# fdcanusb.net
KiCad netlist of a schematic drawn in EAGLE
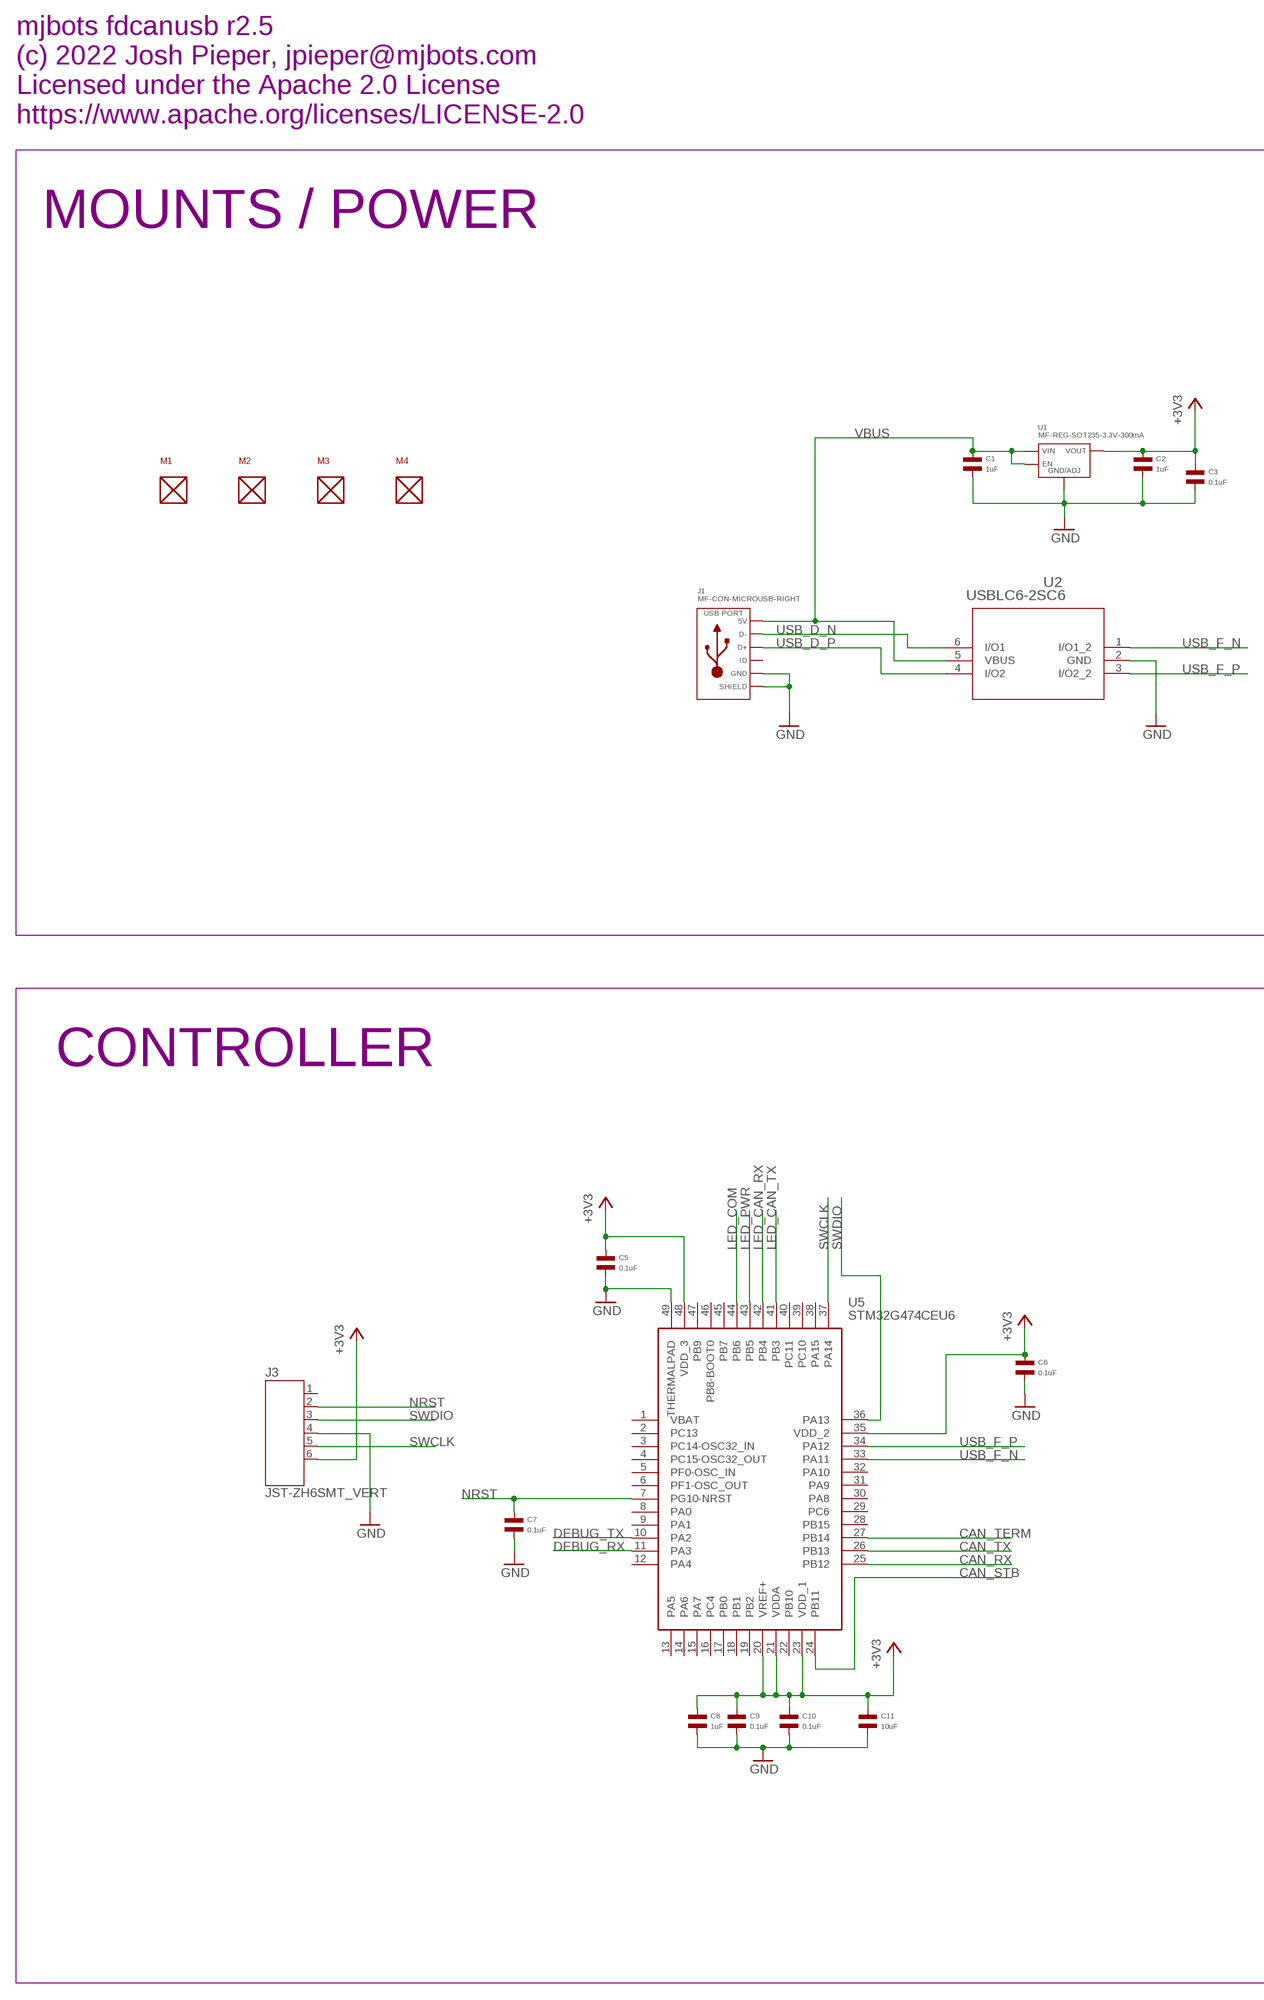
[diagram p0: schematic, sheet 1, part 1 of 2]
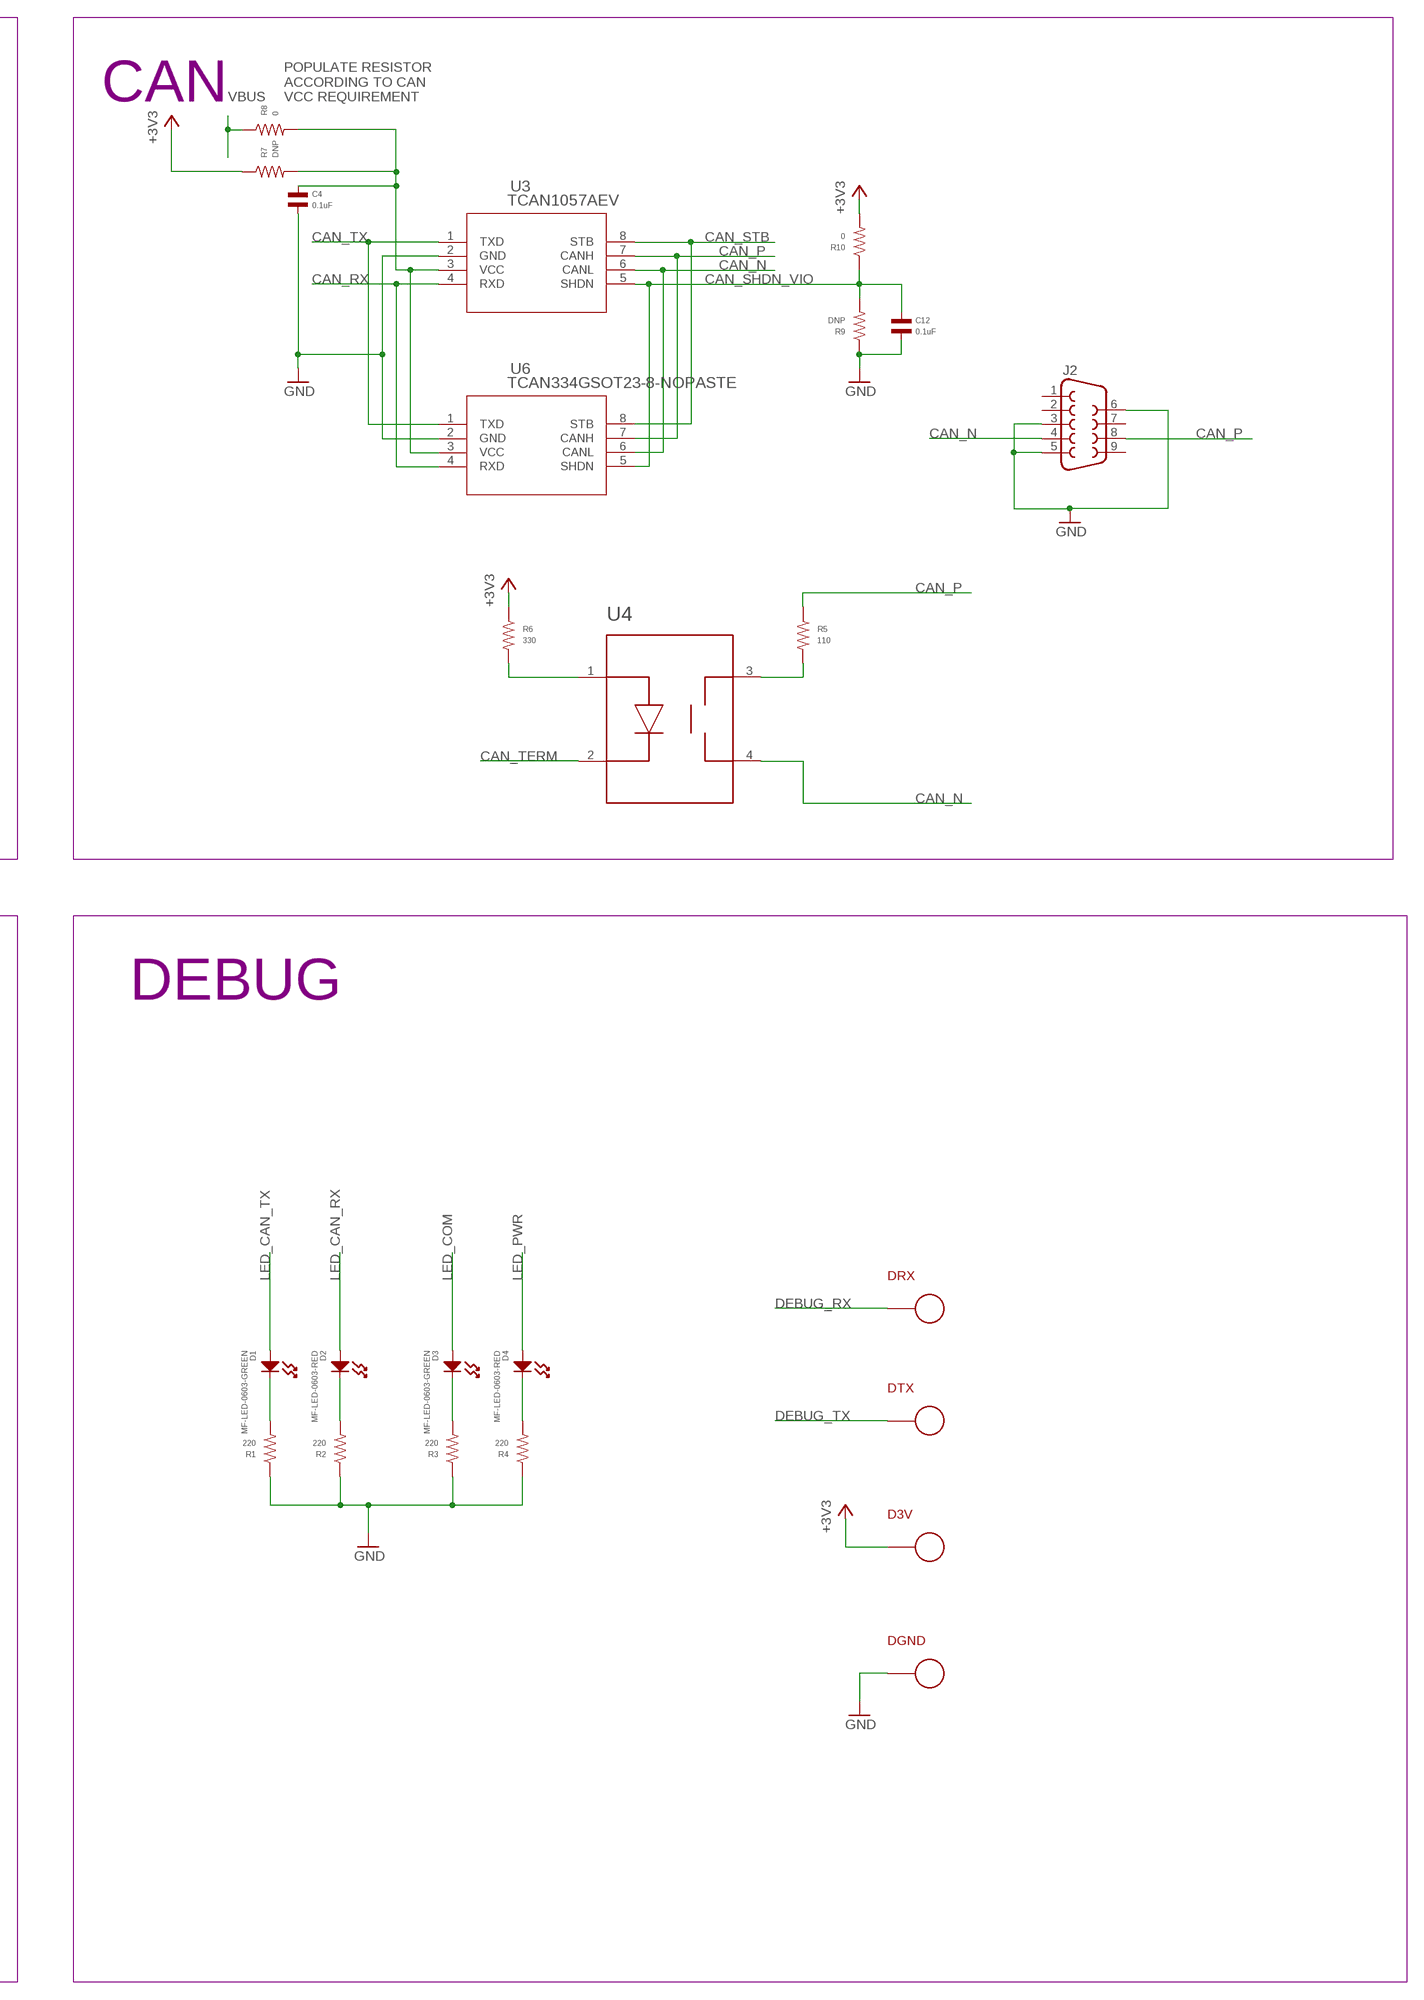
[diagram p1: schematic, sheet 1, part 2 of 2]

(export (version "E")
  (design (tool "Eeschema 10.0.6"))
  (components
    (comp (ref "C1")
      (value "1uF")
      (footprint "eagle-import:C0603")
      (fields (field (name "HOUSEPART") "YES") (field (name "MPN") "MF-CAP-0603-1uF"))
      (libsource (lib "eagle-import") (part "CAPACITOR_NP_0603"))
    )
    (comp (ref "C2")
      (value "1uF")
      (footprint "eagle-import:C0603")
      (fields (field (name "HOUSEPART") "YES") (field (name "MPN") "MF-CAP-0603-1uF"))
      (libsource (lib "eagle-import") (part "CAPACITOR_NP_0603"))
    )
    (comp (ref "C3")
      (value "0.1uF")
      (footprint "eagle-import:C0603")
      (fields (field (name "HOUSEPART") "YES") (field (name "MPN") "MF-CAP-0603-0.1uF"))
      (libsource (lib "eagle-import") (part "CAPACITOR_NP_0603"))
    )
    (comp (ref "C4")
      (value "0.1uF")
      (footprint "eagle-import:C0603")
      (fields (field (name "HOUSEPART") "YES") (field (name "MPN") "MF-CAP-0603-0.1uF"))
      (libsource (lib "eagle-import") (part "CAPACITOR_NP_0603"))
    )
    (comp (ref "C5")
      (value "0.1uF")
      (footprint "eagle-import:C0603")
      (fields (field (name "HOUSEPART") "YES") (field (name "MPN") "MF-CAP-0603-0.1uF"))
      (libsource (lib "eagle-import") (part "CAPACITOR_NP_0603"))
    )
    (comp (ref "C6")
      (value "0.1uF")
      (footprint "eagle-import:C0603")
      (fields (field (name "HOUSEPART") "YES") (field (name "MPN") "MF-CAP-0603-0.1uF"))
      (libsource (lib "eagle-import") (part "CAPACITOR_NP_0603"))
    )
    (comp (ref "C7")
      (value "0.1uF")
      (footprint "eagle-import:C0603")
      (fields (field (name "HOUSEPART") "YES") (field (name "MPN") "MF-CAP-0603-0.1uF"))
      (libsource (lib "eagle-import") (part "CAPACITOR_NP_0603"))
    )
    (comp (ref "C8")
      (value "1uF")
      (footprint "eagle-import:C0603")
      (fields (field (name "HOUSEPART") "YES") (field (name "MPN") "MF-CAP-0603-1uF"))
      (libsource (lib "eagle-import") (part "CAPACITOR_NP_0603"))
    )
    (comp (ref "C9")
      (value "0.1uF")
      (footprint "eagle-import:C0603")
      (fields (field (name "HOUSEPART") "YES") (field (name "MPN") "MF-CAP-0603-0.1uF"))
      (libsource (lib "eagle-import") (part "CAPACITOR_NP_0603"))
    )
    (comp (ref "C10")
      (value "0.1uF")
      (footprint "eagle-import:C0603")
      (fields (field (name "HOUSEPART") "YES") (field (name "MPN") "MF-CAP-0603-0.1uF"))
      (libsource (lib "eagle-import") (part "CAPACITOR_NP_0603"))
    )
    (comp (ref "C11")
      (value "10uF")
      (footprint "eagle-import:C1206")
      (fields (field (name "HOUSEPART") "YES") (field (name "MPN") "MF-CAP-1206-10uF"))
      (libsource (lib "eagle-import") (part "CAPACITOR_NP_1206"))
    )
    (comp (ref "C12")
      (value "0.1uF")
      (footprint "eagle-import:C0603")
      (fields (field (name "HOUSEPART") "YES") (field (name "MPN") "MF-CAP-0603-0.1uF"))
      (libsource (lib "eagle-import") (part "CAPACITOR_NP_0603"))
    )
    (comp (ref "D1")
      (value "MF-LED-0603-GREEN")
      (footprint "eagle-import:LED0603")
      (fields (field (name "HOUSEPART") "YES"))
      (libsource (lib "eagle-import") (part "LED_SINGLE-0603-GREEN"))
    )
    (comp (ref "D2")
      (value "MF-LED-0603-RED")
      (footprint "eagle-import:LED0603")
      (fields (field (name "HOUSEPART") "YES"))
      (libsource (lib "eagle-import") (part "LED_SINGLE-0603-RED"))
    )
    (comp (ref "D3")
      (value "MF-LED-0603-GREEN")
      (footprint "eagle-import:LED0603")
      (fields (field (name "HOUSEPART") "YES"))
      (libsource (lib "eagle-import") (part "LED_SINGLE-0603-GREEN"))
    )
    (comp (ref "D3V")
      (value "PAD24AWG_PAD")
      (footprint "eagle-import:24AWG_PAD")
      (libsource (lib "eagle-import") (part "PAD24AWG_PAD"))
    )
    (comp (ref "D4")
      (value "MF-LED-0603-RED")
      (footprint "eagle-import:LED0603")
      (fields (field (name "HOUSEPART") "YES"))
      (libsource (lib "eagle-import") (part "LED_SINGLE-0603-RED"))
    )
    (comp (ref "DGND")
      (value "PAD24AWG_PAD")
      (footprint "eagle-import:24AWG_PAD")
      (libsource (lib "eagle-import") (part "PAD24AWG_PAD"))
    )
    (comp (ref "DRX")
      (value "PAD24AWG_PAD")
      (footprint "eagle-import:24AWG_PAD")
      (libsource (lib "eagle-import") (part "PAD24AWG_PAD"))
    )
    (comp (ref "DTX")
      (value "PAD24AWG_PAD")
      (footprint "eagle-import:24AWG_PAD")
      (libsource (lib "eagle-import") (part "PAD24AWG_PAD"))
    )
    (comp (ref "J1")
      (value "MF-CON-MICROUSB-RIGHT")
      (footprint "eagle-import:MICROUSB-RIGHT")
      (fields (field (name "HOUSEPART") "YES"))
      (libsource (lib "eagle-import") (part "USB_MICRO_RIGHT"))
    )
    (comp (ref "J2")
      (value "F09")
      (footprint "eagle-import:DB09_PLATED")
      (libsource (lib "eagle-import") (part "F09"))
    )
    (comp (ref "J3")
      (value "JST-ZH6SMT_VERT")
      (footprint "eagle-import:JST_B6B-ZR-SM4-TF(LF)(SN)")
      (fields (field (name "MF") "JST") (field (name "MPN") "B6B-ZR-SM4-TF(LF)(SN)"))
      (libsource (lib "eagle-import") (part "JST-ZH6SMT_VERT"))
    )
    (comp (ref "M1")
      (value "MOUNT")
      (footprint "eagle-import:M2.5MOUNT")
      (libsource (lib "eagle-import") (part "MOUNT"))
    )
    (comp (ref "M2")
      (value "MOUNT")
      (footprint "eagle-import:M2.5MOUNT")
      (libsource (lib "eagle-import") (part "MOUNT"))
    )
    (comp (ref "M3")
      (value "MOUNT")
      (footprint "eagle-import:M2.5MOUNT")
      (libsource (lib "eagle-import") (part "MOUNT"))
    )
    (comp (ref "M4")
      (value "MOUNT")
      (footprint "eagle-import:M2.5MOUNT")
      (libsource (lib "eagle-import") (part "MOUNT"))
    )
    (comp (ref "R1")
      (value "220")
      (footprint "eagle-import:R0603")
      (fields (field (name "HOUSEPART") "YES") (field (name "MPN") "MF-RES-0603-220"))
      (libsource (lib "eagle-import") (part "RESISTOR_0603"))
    )
    (comp (ref "R2")
      (value "220")
      (footprint "eagle-import:R0603")
      (fields (field (name "HOUSEPART") "YES") (field (name "MPN") "MF-RES-0603-220"))
      (libsource (lib "eagle-import") (part "RESISTOR_0603"))
    )
    (comp (ref "R3")
      (value "220")
      (footprint "eagle-import:R0603")
      (fields (field (name "HOUSEPART") "YES") (field (name "MPN") "MF-RES-0603-220"))
      (libsource (lib "eagle-import") (part "RESISTOR_0603"))
    )
    (comp (ref "R4")
      (value "220")
      (footprint "eagle-import:R0603")
      (fields (field (name "HOUSEPART") "YES") (field (name "MPN") "MF-RES-0603-220"))
      (libsource (lib "eagle-import") (part "RESISTOR_0603"))
    )
    (comp (ref "R5")
      (value "110")
      (footprint "eagle-import:R0603")
      (fields (field (name "MF") "YAGEO") (field (name "MPN") "RC0603FR-07110RL"))
      (libsource (lib "eagle-import") (part "RESISTOR_0603"))
    )
    (comp (ref "R6")
      (value "330")
      (footprint "eagle-import:R0603")
      (fields (field (name "HOUSEPART") "YES") (field (name "MPN") "MF-RES-0603-330"))
      (libsource (lib "eagle-import") (part "RESISTOR_0603"))
    )
    (comp (ref "R7")
      (value "DNP")
      (footprint "eagle-import:R0603")
      (fields (field (name "HOUSEPART") "YES") (field (name "POPULATE") "0"))
      (libsource (lib "eagle-import") (part "RESISTOR_0603"))
    )
    (comp (ref "R8")
      (value "0")
      (footprint "eagle-import:R0603")
      (fields (field (name "HOUSEPART") "YES") (field (name "MPN") "MF-RES-0603-0"))
      (libsource (lib "eagle-import") (part "RESISTOR_0603"))
    )
    (comp (ref "R9")
      (value "DNP")
      (footprint "eagle-import:R0603")
      (fields (field (name "HOUSEPART") "YES") (field (name "POPULATE") "0"))
      (libsource (lib "eagle-import") (part "RESISTOR_0603"))
    )
    (comp (ref "R10")
      (value "0")
      (footprint "eagle-import:R0603")
      (fields (field (name "HOUSEPART") "YES") (field (name "MPN") "MF-RES-0603-0"))
      (libsource (lib "eagle-import") (part "RESISTOR_0603"))
    )
    (comp (ref "U1")
      (value "MF-REG-SOT235-3.3V-300mA")
      (footprint "eagle-import:SOT-23-5")
      (fields (field (name "HOUSEPART") "YES"))
      (libsource (lib "eagle-import") (part "TLV70233PDBVR"))
    )
    (comp (ref "U2")
      (value "USBLC6-2SC6")
      (footprint "eagle-import:SOT23-6L")
      (fields (field (name "MANUFACTURER_PART_NUMBER") "USBLC62SC6") (field (name "MF") "ST"))
      (libsource (lib "eagle-import") (part "USBLC6-2SC6"))
    )
    (comp (ref "U3")
      (value "TCAN1057AEV")
      (footprint "eagle-import:SOIC8")
      (fields (field (name "MF") "TI") (field (name "MPN") "TCAN1057AEVDRQ1"))
      (libsource (lib "eagle-import") (part "fdcanusb_TCAN334G"))
    )
    (comp (ref "U4")
      (value "TLP3317")
      (footprint "eagle-import:TLP3317")
      (fields
        (field (name "MF") "TOSHIBA")
        (field (name "MPN") "TLP3317(TP15,F")
        (field (name "MPN_1") "TLP3317")
      )
      (libsource (lib "eagle-import") (part "TLP3317"))
    )
    (comp (ref "U5")
      (value "STM32G474CEU6")
      (footprint "eagle-import:QFN50P700X700X60-49N")
      (fields (field (name "MOUSER_PART_NUMBER") "511-STM32G474CEU6") (field (name "MF") "ST"))
      (libsource (lib "eagle-import") (part "STM32G474CEU6"))
    )
    (comp (ref "U6")
      (value "TCAN334GSOT23-8-NOPASTE")
      (footprint "eagle-import:SOT23-8-NOPASTE")
      (fields (field (name "MF") "TI") (field (name "MPN") "TCAN334GDCNT"))
      (libsource (lib "eagle-import") (part "TCAN334GSOT23-8-NOPASTE"))
    )
  )
  (nets
    (net (code "1") (name "+3V3") (class "Default")
      (node (ref "C10") (pin "P$1") (pinfunction "P$1_P$1") (pintype "passive"))
      (node (ref "C11") (pin "P$1") (pinfunction "P$1_P$1") (pintype "passive"))
      (node (ref "C2") (pin "P$1") (pinfunction "P$1_P$1") (pintype "passive"))
      (node (ref "C3") (pin "P$1") (pinfunction "P$1_P$1") (pintype "passive"))
      (node (ref "C5") (pin "P$1") (pinfunction "P$1_P$1") (pintype "passive"))
      (node (ref "C6") (pin "P$1") (pinfunction "P$1_P$1") (pintype "passive"))
      (node (ref "C8") (pin "P$1") (pinfunction "P$1_P$1") (pintype "passive"))
      (node (ref "C9") (pin "P$1") (pinfunction "P$1_P$1") (pintype "passive"))
      (node (ref "D3V") (pin "P$1") (pinfunction "P$1_P$1") (pintype "bidirectional"))
      (node (ref "J3") (pin "6") (pinfunction "6_6") (pintype "passive"))
      (node (ref "R10") (pin "P$2") (pinfunction "P$2_P$2") (pintype "passive"))
      (node (ref "R6") (pin "P$1") (pinfunction "P$1_P$1") (pintype "passive"))
      (node (ref "R7") (pin "P$1") (pinfunction "P$1_P$1") (pintype "passive"))
      (node (ref "U1") (pin "P$5") (pinfunction "VOUT_P$5") (pintype "bidirectional"))
      (node (ref "U5") (pin "20") (pinfunction "VREF+_20") (pintype "bidirectional"))
      (node (ref "U5") (pin "21") (pinfunction "VDDA_21") (pintype "bidirectional"))
      (node (ref "U5") (pin "23") (pinfunction "VDD_1_23") (pintype "bidirectional"))
      (node (ref "U5") (pin "35") (pinfunction "VDD_2_35") (pintype "bidirectional"))
      (node (ref "U5") (pin "48") (pinfunction "VDD_3_48") (pintype "bidirectional"))
    )
    (net (code "2") (name "/CAN_N") (class "Default")
      (node (ref "J2") (pin "4") (pinfunction "4_4") (pintype "passive"))
      (node (ref "U3") (pin "6") (pinfunction "CANL_6") (pintype "bidirectional"))
      (node (ref "U4") (pin "4") (pinfunction "SW2_4") (pintype "bidirectional"))
      (node (ref "U6") (pin "6") (pinfunction "CANL_6") (pintype "bidirectional"))
    )
    (net (code "3") (name "/CAN_P") (class "Default")
      (node (ref "J2") (pin "8") (pinfunction "8_8") (pintype "passive"))
      (node (ref "R5") (pin "P$1") (pinfunction "P$1_P$1") (pintype "passive"))
      (node (ref "U3") (pin "7") (pinfunction "CANH_7") (pintype "bidirectional"))
      (node (ref "U6") (pin "7") (pinfunction "CANH_7") (pintype "bidirectional"))
    )
    (net (code "4") (name "/CAN_RX") (class "Default")
      (node (ref "U3") (pin "4") (pinfunction "RXD_4") (pintype "output"))
      (node (ref "U5") (pin "25") (pinfunction "PB12_25") (pintype "bidirectional"))
      (node (ref "U6") (pin "4") (pinfunction "RXD_4") (pintype "output"))
    )
    (net (code "5") (name "/CAN_SHDN_VIO") (class "Default")
      (node (ref "C12") (pin "P$1") (pinfunction "P$1_P$1") (pintype "passive"))
      (node (ref "R10") (pin "P$1") (pinfunction "P$1_P$1") (pintype "passive"))
      (node (ref "R9") (pin "P$2") (pinfunction "P$2_P$2") (pintype "passive"))
      (node (ref "U3") (pin "5") (pinfunction "SHDN_5") (pintype "input"))
      (node (ref "U6") (pin "5") (pinfunction "SHDN_5") (pintype "input"))
    )
    (net (code "6") (name "/CAN_STB") (class "Default")
      (node (ref "U3") (pin "8") (pinfunction "STB_8") (pintype "input"))
      (node (ref "U5") (pin "24") (pinfunction "PB11_24") (pintype "bidirectional"))
      (node (ref "U6") (pin "8") (pinfunction "STB_8") (pintype "input"))
    )
    (net (code "7") (name "/CAN_TERM") (class "Default")
      (node (ref "U4") (pin "2") (pinfunction "CATHODE_2") (pintype "bidirectional"))
      (node (ref "U5") (pin "27") (pinfunction "PB14_27") (pintype "bidirectional"))
    )
    (net (code "8") (name "/CAN_TX") (class "Default")
      (node (ref "U3") (pin "1") (pinfunction "TXD_1") (pintype "input"))
      (node (ref "U5") (pin "26") (pinfunction "PB13_26") (pintype "bidirectional"))
      (node (ref "U6") (pin "1") (pinfunction "TXD_1") (pintype "input"))
    )
    (net (code "9") (name "/DEBUG_RX") (class "Default")
      (node (ref "DRX") (pin "P$1") (pinfunction "P$1_P$1") (pintype "bidirectional"))
      (node (ref "U5") (pin "11") (pinfunction "PA3_11") (pintype "bidirectional"))
    )
    (net (code "10") (name "/DEBUG_TX") (class "Default")
      (node (ref "DTX") (pin "P$1") (pinfunction "P$1_P$1") (pintype "bidirectional"))
      (node (ref "U5") (pin "10") (pinfunction "PA2_10") (pintype "bidirectional"))
    )
    (net (code "11") (name "/LED_CAN_RX") (class "Default")
      (node (ref "D2") (pin "ANODE") (pinfunction "ANODE_ANODE") (pintype "power_in"))
      (node (ref "U5") (pin "42") (pinfunction "PB4_42") (pintype "bidirectional"))
    )
    (net (code "12") (name "/LED_CAN_TX") (class "Default")
      (node (ref "D1") (pin "ANODE") (pinfunction "ANODE_ANODE") (pintype "power_in"))
      (node (ref "U5") (pin "41") (pinfunction "PB3_41") (pintype "bidirectional"))
    )
    (net (code "13") (name "/LED_COM") (class "Default")
      (node (ref "D3") (pin "ANODE") (pinfunction "ANODE_ANODE") (pintype "power_in"))
      (node (ref "U5") (pin "44") (pinfunction "PB6_44") (pintype "bidirectional"))
    )
    (net (code "14") (name "/LED_PWR") (class "Default")
      (node (ref "D4") (pin "ANODE") (pinfunction "ANODE_ANODE") (pintype "power_in"))
      (node (ref "U5") (pin "43") (pinfunction "PB5_43") (pintype "bidirectional"))
    )
    (net (code "15") (name "/NRST") (class "Default")
      (node (ref "C7") (pin "P$1") (pinfunction "P$1_P$1") (pintype "passive"))
      (node (ref "J3") (pin "2") (pinfunction "2_2") (pintype "passive"))
      (node (ref "U5") (pin "7") (pinfunction "PG10-NRST_7") (pintype "bidirectional"))
    )
    (net (code "16") (name "/SWCLK") (class "Default")
      (node (ref "J3") (pin "5") (pinfunction "5_5") (pintype "passive"))
      (node (ref "U5") (pin "37") (pinfunction "PA14_37") (pintype "bidirectional"))
    )
    (net (code "17") (name "/SWDIO") (class "Default")
      (node (ref "J3") (pin "3") (pinfunction "3_3") (pintype "passive"))
      (node (ref "U5") (pin "36") (pinfunction "PA13_36") (pintype "bidirectional"))
    )
    (net (code "18") (name "/USB_D_N") (class "Default")
      (node (ref "J1") (pin "2") (pinfunction "D-_2") (pintype "bidirectional"))
      (node (ref "U2") (pin "6") (pinfunction "I/O1_6") (pintype "bidirectional"))
    )
    (net (code "19") (name "/USB_D_P") (class "Default")
      (node (ref "J1") (pin "3") (pinfunction "D+_3") (pintype "bidirectional"))
      (node (ref "U2") (pin "4") (pinfunction "I/O2_4") (pintype "bidirectional"))
    )
    (net (code "20") (name "/USB_F_N") (class "Default")
      (node (ref "U2") (pin "1") (pinfunction "I/O1_2_1") (pintype "bidirectional"))
      (node (ref "U5") (pin "33") (pinfunction "PA11_33") (pintype "bidirectional"))
    )
    (net (code "21") (name "/USB_F_P") (class "Default")
      (node (ref "U2") (pin "3") (pinfunction "I/O2_2_3") (pintype "bidirectional"))
      (node (ref "U5") (pin "34") (pinfunction "PA12_34") (pintype "bidirectional"))
    )
    (net (code "22") (name "/VBUS") (class "Default")
      (node (ref "C1") (pin "P$1") (pinfunction "P$1_P$1") (pintype "passive"))
      (node (ref "J1") (pin "1") (pinfunction "5V_1") (pintype "power_in"))
      (node (ref "R8") (pin "P$1") (pinfunction "P$1_P$1") (pintype "passive"))
      (node (ref "U1") (pin "P$1") (pinfunction "VIN_P$1") (pintype "bidirectional"))
      (node (ref "U1") (pin "P$3") (pinfunction "EN_P$3") (pintype "bidirectional"))
      (node (ref "U2") (pin "5") (pinfunction "VBUS_5") (pintype "power_in"))
    )
    (net (code "23") (name "GND") (class "Default")
      (node (ref "C1") (pin "P$2") (pinfunction "P$2_P$2") (pintype "passive"))
      (node (ref "C10") (pin "P$2") (pinfunction "P$2_P$2") (pintype "passive"))
      (node (ref "C11") (pin "P$2") (pinfunction "P$2_P$2") (pintype "passive"))
      (node (ref "C12") (pin "P$2") (pinfunction "P$2_P$2") (pintype "passive"))
      (node (ref "C2") (pin "P$2") (pinfunction "P$2_P$2") (pintype "passive"))
      (node (ref "C3") (pin "P$2") (pinfunction "P$2_P$2") (pintype "passive"))
      (node (ref "C4") (pin "P$2") (pinfunction "P$2_P$2") (pintype "passive"))
      (node (ref "C5") (pin "P$2") (pinfunction "P$2_P$2") (pintype "passive"))
      (node (ref "C6") (pin "P$2") (pinfunction "P$2_P$2") (pintype "passive"))
      (node (ref "C7") (pin "P$2") (pinfunction "P$2_P$2") (pintype "passive"))
      (node (ref "C8") (pin "P$2") (pinfunction "P$2_P$2") (pintype "passive"))
      (node (ref "C9") (pin "P$2") (pinfunction "P$2_P$2") (pintype "passive"))
      (node (ref "DGND") (pin "P$1") (pinfunction "P$1_P$1") (pintype "bidirectional"))
      (node (ref "J1") (pin "5") (pinfunction "GND_5") (pintype "power_in"))
      (node (ref "J1") (pin "S1") (pinfunction "SLD_S1") (pintype "power_in"))
      (node (ref "J1") (pin "S2") (pinfunction "SLD_S2") (pintype "power_in"))
      (node (ref "J1") (pin "S3") (pinfunction "SLD_S3") (pintype "power_in"))
      (node (ref "J1") (pin "S4") (pinfunction "SLD_S4") (pintype "power_in"))
      (node (ref "J1") (pin "S5") (pinfunction "SLD_S5") (pintype "power_in"))
      (node (ref "J1") (pin "S6") (pinfunction "SLD_S6") (pintype "power_in"))
      (node (ref "J2") (pin "3") (pinfunction "3_3") (pintype "passive"))
      (node (ref "J2") (pin "5") (pinfunction "5_5") (pintype "passive"))
      (node (ref "J2") (pin "6") (pinfunction "6_6") (pintype "passive"))
      (node (ref "J3") (pin "4") (pinfunction "4_4") (pintype "passive"))
      (node (ref "R1") (pin "P$1") (pinfunction "P$1_P$1") (pintype "passive"))
      (node (ref "R2") (pin "P$1") (pinfunction "P$1_P$1") (pintype "passive"))
      (node (ref "R3") (pin "P$1") (pinfunction "P$1_P$1") (pintype "passive"))
      (node (ref "R4") (pin "P$1") (pinfunction "P$1_P$1") (pintype "passive"))
      (node (ref "R9") (pin "P$1") (pinfunction "P$1_P$1") (pintype "passive"))
      (node (ref "U1") (pin "P$2") (pinfunction "GND/ADJ_P$2") (pintype "bidirectional"))
      (node (ref "U2") (pin "2") (pinfunction "GND_2") (pintype "power_in"))
      (node (ref "U3") (pin "2") (pinfunction "GND_2") (pintype "power_in"))
      (node (ref "U5") (pin "49") (pinfunction "THERMALPAD_49") (pintype "bidirectional"))
      (node (ref "U6") (pin "2") (pinfunction "GND_2") (pintype "power_in"))
    )
    (net (code "24") (name "Net-(D1-PadCATHODE)") (class "Default")
      (node (ref "D1") (pin "CATHODE") (pinfunction "CATHODE_CATHODE") (pintype "power_in"))
      (node (ref "R1") (pin "P$2") (pinfunction "P$2_P$2") (pintype "passive"))
    )
    (net (code "25") (name "Net-(D2-PadCATHODE)") (class "Default")
      (node (ref "D2") (pin "CATHODE") (pinfunction "CATHODE_CATHODE") (pintype "power_in"))
      (node (ref "R2") (pin "P$2") (pinfunction "P$2_P$2") (pintype "passive"))
    )
    (net (code "26") (name "Net-(D3-PadCATHODE)") (class "Default")
      (node (ref "D3") (pin "CATHODE") (pinfunction "CATHODE_CATHODE") (pintype "power_in"))
      (node (ref "R3") (pin "P$2") (pinfunction "P$2_P$2") (pintype "passive"))
    )
    (net (code "27") (name "Net-(D4-PadCATHODE)") (class "Default")
      (node (ref "D4") (pin "CATHODE") (pinfunction "CATHODE_CATHODE") (pintype "power_in"))
      (node (ref "R4") (pin "P$2") (pinfunction "P$2_P$2") (pintype "passive"))
    )
    (net (code "28") (name "Net-(U3-VCC)") (class "Default")
      (node (ref "C4") (pin "P$1") (pinfunction "P$1_P$1") (pintype "passive"))
      (node (ref "R7") (pin "P$2") (pinfunction "P$2_P$2") (pintype "passive"))
      (node (ref "R8") (pin "P$2") (pinfunction "P$2_P$2") (pintype "passive"))
      (node (ref "U3") (pin "3") (pinfunction "VCC_3") (pintype "power_in"))
      (node (ref "U6") (pin "3") (pinfunction "VCC_3") (pintype "power_in"))
    )
    (net (code "29") (name "Net-(U4-ANODE)") (class "Default")
      (node (ref "R6") (pin "P$2") (pinfunction "P$2_P$2") (pintype "passive"))
      (node (ref "U4") (pin "1") (pinfunction "ANODE_1") (pintype "bidirectional"))
    )
    (net (code "30") (name "Net-(U4-SW1)") (class "Default")
      (node (ref "R5") (pin "P$2") (pinfunction "P$2_P$2") (pintype "passive"))
      (node (ref "U4") (pin "3") (pinfunction "SW1_3") (pintype "bidirectional"))
    )
    (net (code "31") (name "unconnected-(J1-ID-Pad4)") (class "Default")
      (node (ref "J1") (pin "4") (pinfunction "ID_4") (pintype "bidirectional"))
    )
    (net (code "32") (name "unconnected-(J2-Pad1)") (class "Default")
      (node (ref "J2") (pin "1") (pinfunction "1_1") (pintype "passive"))
    )
    (net (code "33") (name "unconnected-(J2-Pad2)") (class "Default")
      (node (ref "J2") (pin "2") (pinfunction "2_2") (pintype "passive"))
    )
    (net (code "34") (name "unconnected-(J2-Pad7)") (class "Default")
      (node (ref "J2") (pin "7") (pinfunction "7_7") (pintype "passive"))
    )
    (net (code "35") (name "unconnected-(J2-Pad9)") (class "Default")
      (node (ref "J2") (pin "9") (pinfunction "9_9") (pintype "passive"))
    )
    (net (code "36") (name "unconnected-(J3-Pad1)") (class "Default")
      (node (ref "J3") (pin "1") (pinfunction "1_1") (pintype "passive"))
    )
    (net (code "37") (name "unconnected-(U5-PA0-Pad8)") (class "Default")
      (node (ref "U5") (pin "8") (pinfunction "PA0_8") (pintype "bidirectional"))
    )
    (net (code "38") (name "unconnected-(U5-PA1-Pad9)") (class "Default")
      (node (ref "U5") (pin "9") (pinfunction "PA1_9") (pintype "bidirectional"))
    )
    (net (code "39") (name "unconnected-(U5-PA4-Pad12)") (class "Default")
      (node (ref "U5") (pin "12") (pinfunction "PA4_12") (pintype "bidirectional"))
    )
    (net (code "40") (name "unconnected-(U5-PA5-Pad13)") (class "Default")
      (node (ref "U5") (pin "13") (pinfunction "PA5_13") (pintype "bidirectional"))
    )
    (net (code "41") (name "unconnected-(U5-PA6-Pad14)") (class "Default")
      (node (ref "U5") (pin "14") (pinfunction "PA6_14") (pintype "bidirectional"))
    )
    (net (code "42") (name "unconnected-(U5-PA7-Pad15)") (class "Default")
      (node (ref "U5") (pin "15") (pinfunction "PA7_15") (pintype "bidirectional"))
    )
    (net (code "43") (name "unconnected-(U5-PA8-Pad30)") (class "Default")
      (node (ref "U5") (pin "30") (pinfunction "PA8_30") (pintype "bidirectional"))
    )
    (net (code "44") (name "unconnected-(U5-PA9-Pad31)") (class "Default")
      (node (ref "U5") (pin "31") (pinfunction "PA9_31") (pintype "bidirectional"))
    )
    (net (code "45") (name "unconnected-(U5-PA10-Pad32)") (class "Default")
      (node (ref "U5") (pin "32") (pinfunction "PA10_32") (pintype "bidirectional"))
    )
    (net (code "46") (name "unconnected-(U5-PA15-Pad38)") (class "Default")
      (node (ref "U5") (pin "38") (pinfunction "PA15_38") (pintype "bidirectional"))
    )
    (net (code "47") (name "unconnected-(U5-PB0-Pad17)") (class "Default")
      (node (ref "U5") (pin "17") (pinfunction "PB0_17") (pintype "bidirectional"))
    )
    (net (code "48") (name "unconnected-(U5-PB1-Pad18)") (class "Default")
      (node (ref "U5") (pin "18") (pinfunction "PB1_18") (pintype "bidirectional"))
    )
    (net (code "49") (name "unconnected-(U5-PB2-Pad19)") (class "Default")
      (node (ref "U5") (pin "19") (pinfunction "PB2_19") (pintype "bidirectional"))
    )
    (net (code "50") (name "unconnected-(U5-PB7-Pad45)") (class "Default")
      (node (ref "U5") (pin "45") (pinfunction "PB7_45") (pintype "bidirectional"))
    )
    (net (code "51") (name "unconnected-(U5-PB8-BOOT0-Pad46)") (class "Default")
      (node (ref "U5") (pin "46") (pinfunction "PB8-BOOT0_46") (pintype "bidirectional"))
    )
    (net (code "52") (name "unconnected-(U5-PB9-Pad47)") (class "Default")
      (node (ref "U5") (pin "47") (pinfunction "PB9_47") (pintype "bidirectional"))
    )
    (net (code "53") (name "unconnected-(U5-PB10-Pad22)") (class "Default")
      (node (ref "U5") (pin "22") (pinfunction "PB10_22") (pintype "bidirectional"))
    )
    (net (code "54") (name "unconnected-(U5-PB15-Pad28)") (class "Default")
      (node (ref "U5") (pin "28") (pinfunction "PB15_28") (pintype "bidirectional"))
    )
    (net (code "55") (name "unconnected-(U5-PC4-Pad16)") (class "Default")
      (node (ref "U5") (pin "16") (pinfunction "PC4_16") (pintype "bidirectional"))
    )
    (net (code "56") (name "unconnected-(U5-PC6-Pad29)") (class "Default")
      (node (ref "U5") (pin "29") (pinfunction "PC6_29") (pintype "bidirectional"))
    )
    (net (code "57") (name "unconnected-(U5-PC10-Pad39)") (class "Default")
      (node (ref "U5") (pin "39") (pinfunction "PC10_39") (pintype "bidirectional"))
    )
    (net (code "58") (name "unconnected-(U5-PC11-Pad40)") (class "Default")
      (node (ref "U5") (pin "40") (pinfunction "PC11_40") (pintype "bidirectional"))
    )
    (net (code "59") (name "unconnected-(U5-PC13-Pad2)") (class "Default")
      (node (ref "U5") (pin "2") (pinfunction "PC13_2") (pintype "bidirectional"))
    )
    (net (code "60") (name "unconnected-(U5-PC14-OSC32_IN-Pad3)") (class "Default")
      (node (ref "U5") (pin "3") (pinfunction "PC14-OSC32_IN_3") (pintype "bidirectional"))
    )
    (net (code "61") (name "unconnected-(U5-PC15-OSC32_OUT-Pad4)") (class "Default")
      (node (ref "U5") (pin "4") (pinfunction "PC15-OSC32_OUT_4") (pintype "bidirectional"))
    )
    (net (code "62") (name "unconnected-(U5-PF0-OSC_IN-Pad5)") (class "Default")
      (node (ref "U5") (pin "5") (pinfunction "PF0-OSC_IN_5") (pintype "bidirectional"))
    )
    (net (code "63") (name "unconnected-(U5-PF1-OSC_OUT-Pad6)") (class "Default")
      (node (ref "U5") (pin "6") (pinfunction "PF1-OSC_OUT_6") (pintype "bidirectional"))
    )
    (net (code "64") (name "unconnected-(U5-VBAT-Pad1)") (class "Default")
      (node (ref "U5") (pin "1") (pinfunction "VBAT_1") (pintype "bidirectional"))
    )
  )
)
